# Sheet2.net
KiCad netlist of a schematic drawn in Altium Designer
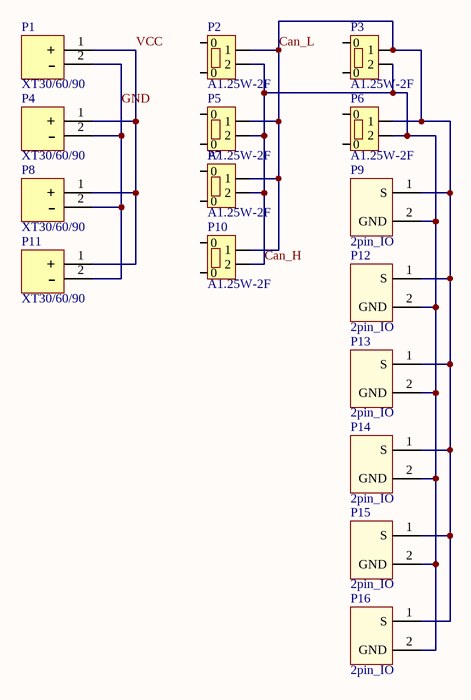
[diagram p0: Sheet2.SchDoc]

(export (version "E")
  (design (tool "Eeschema 10.0.6"))
  (components
    (comp (ref "P1")
      (value "XT30/60/90")
      (footprint "XT30UPB-FEMALE")
      (libsource (lib "MyComponents_v2.5") (part "XT30/60/90"))
    )
    (comp (ref "P2")
      (value "A1.25W-2F")
      (footprint "GH1.25-2P-立贴")
      (libsource (lib "MyComponents_v2.5") (part "GH1.25-2P"))
    )
    (comp (ref "P3")
      (value "A1.25W-2F")
      (footprint "GH1.25-2P-立贴")
      (libsource (lib "MyComponents_v2.5") (part "GH1.25-2P"))
    )
    (comp (ref "P4")
      (value "XT30/60/90")
      (footprint "XT30UPB-FEMALE")
      (libsource (lib "MyComponents_v2.5") (part "XT30/60/90"))
    )
    (comp (ref "P5")
      (value "A1.25W-2F")
      (footprint "GH1.25-2P-立贴")
      (libsource (lib "MyComponents_v2.5") (part "GH1.25-2P"))
    )
    (comp (ref "P6")
      (value "A1.25W-2F")
      (footprint "GH1.25-2P-立贴")
      (libsource (lib "MyComponents_v2.5") (part "GH1.25-2P"))
    )
    (comp (ref "P7")
      (value "A1.25W-2F")
      (footprint "GH1.25-2P-立贴")
      (libsource (lib "MyComponents_v2.5") (part "GH1.25-2P"))
    )
    (comp (ref "P8")
      (value "XT30/60/90")
      (footprint "XT30UPB-FEMALE")
      (libsource (lib "MyComponents_v2.5") (part "XT30/60/90"))
    )
    (comp (ref "P9")
      (value "2pin_IO")
      (footprint "HY2.00MM 2X1_立式")
      (libsource (lib "MyComponents_v2.5") (part "2pin_IO"))
    )
    (comp (ref "P10")
      (value "A1.25W-2F")
      (footprint "GH1.25-2P-立贴")
      (libsource (lib "MyComponents_v2.5") (part "GH1.25-2P"))
    )
    (comp (ref "P11")
      (value "XT30/60/90")
      (footprint "XT30UPB-FEMALE")
      (libsource (lib "MyComponents_v2.5") (part "XT30/60/90"))
    )
    (comp (ref "P12")
      (value "2pin_IO")
      (footprint "HY2.00MM 2X1_立式")
      (libsource (lib "MyComponents_v2.5") (part "2pin_IO"))
    )
    (comp (ref "P13")
      (value "2pin_IO")
      (footprint "HY2.00MM 2X1_立式")
      (libsource (lib "MyComponents_v2.5") (part "2pin_IO"))
    )
    (comp (ref "P14")
      (value "2pin_IO")
      (footprint "HY2.00MM 2X1_立式")
      (libsource (lib "MyComponents_v2.5") (part "2pin_IO"))
    )
    (comp (ref "P15")
      (value "2pin_IO")
      (footprint "HY2.00MM 2X1_立式")
      (libsource (lib "MyComponents_v2.5") (part "2pin_IO"))
    )
    (comp (ref "P16")
      (value "2pin_IO")
      (footprint "HY2.00MM 2X1_立式")
      (libsource (lib "MyComponents_v2.5") (part "2pin_IO"))
    )
  )
  (nets
    (net (code "1") (name "/Can_H") (class "Default")
      (node (ref "P10") (pin "2") (pinfunction "2_2") (pintype "passive"))
      (node (ref "P12") (pin "2") (pinfunction "GND_2") (pintype "passive"))
      (node (ref "P13") (pin "2") (pinfunction "GND_2") (pintype "passive"))
      (node (ref "P14") (pin "2") (pinfunction "GND_2") (pintype "passive"))
      (node (ref "P15") (pin "2") (pinfunction "GND_2") (pintype "passive"))
      (node (ref "P16") (pin "2") (pinfunction "GND_2") (pintype "passive"))
      (node (ref "P2") (pin "2") (pinfunction "2_2") (pintype "passive"))
      (node (ref "P3") (pin "2") (pinfunction "2_2") (pintype "passive"))
      (node (ref "P5") (pin "2") (pinfunction "2_2") (pintype "passive"))
      (node (ref "P6") (pin "2") (pinfunction "2_2") (pintype "passive"))
      (node (ref "P7") (pin "2") (pinfunction "2_2") (pintype "passive"))
      (node (ref "P9") (pin "2") (pinfunction "GND_2") (pintype "passive"))
    )
    (net (code "2") (name "/Can_L") (class "Default")
      (node (ref "P10") (pin "1") (pinfunction "1_1") (pintype "passive"))
      (node (ref "P12") (pin "1") (pinfunction "S_1") (pintype "passive"))
      (node (ref "P13") (pin "1") (pinfunction "S_1") (pintype "passive"))
      (node (ref "P14") (pin "1") (pinfunction "S_1") (pintype "passive"))
      (node (ref "P15") (pin "1") (pinfunction "S_1") (pintype "passive"))
      (node (ref "P16") (pin "1") (pinfunction "S_1") (pintype "passive"))
      (node (ref "P2") (pin "1") (pinfunction "1_1") (pintype "passive"))
      (node (ref "P3") (pin "1") (pinfunction "1_1") (pintype "passive"))
      (node (ref "P5") (pin "1") (pinfunction "1_1") (pintype "passive"))
      (node (ref "P6") (pin "1") (pinfunction "1_1") (pintype "passive"))
      (node (ref "P7") (pin "1") (pinfunction "1_1") (pintype "passive"))
      (node (ref "P9") (pin "1") (pinfunction "S_1") (pintype "passive"))
    )
    (net (code "3") (name "/GND") (class "Default")
      (node (ref "P1") (pin "2") (pinfunction "-_2") (pintype "passive"))
      (node (ref "P11") (pin "2") (pinfunction "-_2") (pintype "passive"))
      (node (ref "P4") (pin "2") (pinfunction "-_2") (pintype "passive"))
      (node (ref "P8") (pin "2") (pinfunction "-_2") (pintype "passive"))
    )
    (net (code "4") (name "/VCC") (class "Default")
      (node (ref "P1") (pin "1") (pinfunction "+_1") (pintype "passive"))
      (node (ref "P11") (pin "1") (pinfunction "+_1") (pintype "passive"))
      (node (ref "P4") (pin "1") (pinfunction "+_1") (pintype "passive"))
      (node (ref "P8") (pin "1") (pinfunction "+_1") (pintype "passive"))
    )
    (net (code "5") (name "unconnected-(P2-Pad0)") (class "Default")
      (node (ref "P2") (pin "0") (pinfunction "0_0") (pintype "passive"))
    )
    (net (code "6") (name "unconnected-(P2-Pad0)_1") (class "Default")
      (node (ref "P2") (pin "0") (pinfunction "0_0") (pintype "passive"))
    )
    (net (code "7") (name "unconnected-(P3-Pad0)") (class "Default")
      (node (ref "P3") (pin "0") (pinfunction "0_0") (pintype "passive"))
    )
    (net (code "8") (name "unconnected-(P3-Pad0)_1") (class "Default")
      (node (ref "P3") (pin "0") (pinfunction "0_0") (pintype "passive"))
    )
    (net (code "9") (name "unconnected-(P5-Pad0)") (class "Default")
      (node (ref "P5") (pin "0") (pinfunction "0_0") (pintype "passive"))
    )
    (net (code "10") (name "unconnected-(P5-Pad0)_1") (class "Default")
      (node (ref "P5") (pin "0") (pinfunction "0_0") (pintype "passive"))
    )
    (net (code "11") (name "unconnected-(P6-Pad0)") (class "Default")
      (node (ref "P6") (pin "0") (pinfunction "0_0") (pintype "passive"))
    )
    (net (code "12") (name "unconnected-(P6-Pad0)_1") (class "Default")
      (node (ref "P6") (pin "0") (pinfunction "0_0") (pintype "passive"))
    )
    (net (code "13") (name "unconnected-(P7-Pad0)") (class "Default")
      (node (ref "P7") (pin "0") (pinfunction "0_0") (pintype "passive"))
    )
    (net (code "14") (name "unconnected-(P7-Pad0)_1") (class "Default")
      (node (ref "P7") (pin "0") (pinfunction "0_0") (pintype "passive"))
    )
    (net (code "15") (name "unconnected-(P10-Pad0)") (class "Default")
      (node (ref "P10") (pin "0") (pinfunction "0_0") (pintype "passive"))
    )
    (net (code "16") (name "unconnected-(P10-Pad0)_1") (class "Default")
      (node (ref "P10") (pin "0") (pinfunction "0_0") (pintype "passive"))
    )
  )
)
